# Power_supply.net
KiCad netlist of a schematic drawn in Altium Designer
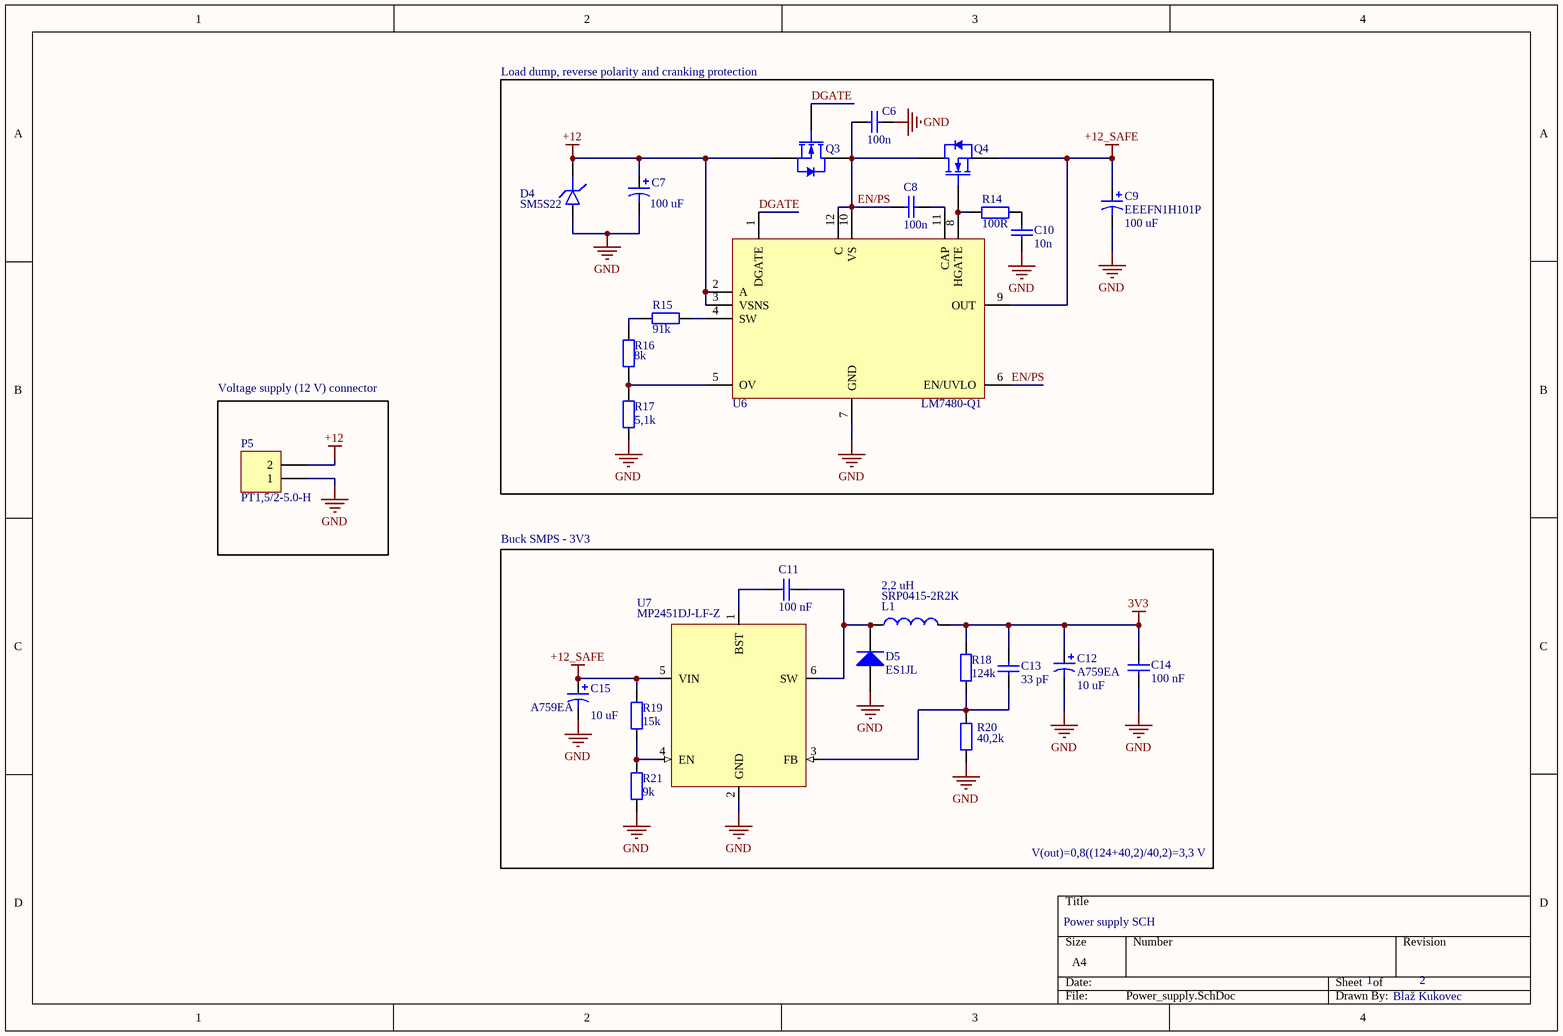
[diagram p0: Power_supply.SchDoc]

(export (version "E")
  (design (tool "Eeschema 10.0.6"))
  (components
    (comp (ref "C6")
      (value "100n")
      (footprint "C0603[1608]")
      (description "Capacitor")
      (fields (field (name "Comment") "Cap"))
      (libsource (lib "BK_Library") (part "Cap"))
    )
    (comp (ref "C7")
      (value "100 uF")
      (footprint "CAP_FN_F_PAN")
      (description "SMD Aluminium Electrolytic Capacitor, Radial Can - SMD, 100 µF, 50 V, 0.34 ohm")
      (fields (field (name "Comment") "EEEFN1H101P"))
      (libsource (lib "BK_Library") (part "EEEFN1H101P"))
    )
    (comp (ref "C8")
      (value "100n")
      (footprint "C0603[1608]")
      (description "Capacitor")
      (fields (field (name "Comment") "Cap"))
      (libsource (lib "BK_Library") (part "Cap"))
    )
    (comp (ref "C9")
      (value "EEEFN1H101P")
      (footprint "CAP_FN_F_PAN")
      (description "SMD Aluminium Electrolytic Capacitor, Radial Can - SMD, 100 µF, 50 V, 0.34 ohm")
      (fields (field (name "ALTIUM_VALUE") "100 uF"))
      (libsource (lib "") (part "EEEFN1H101P_1"))
    )
    (comp (ref "C10")
      (value "10n")
      (footprint "C0603[1608]")
      (description "Capacitor")
      (fields (field (name "Comment") "Cap"))
      (libsource (lib "BK_Library") (part "Cap"))
    )
    (comp (ref "C11")
      (value "100 nF")
      (footprint "C0603[1608]")
      (description "Capacitor")
      (fields (field (name "Comment") "Cap"))
      (libsource (lib "BK_Library") (part "Cap"))
    )
    (comp (ref "C12")
      (value "A759EA")
      (footprint "A759EA")
      (description "A759EA106M1JAAE060 - Capacitor - 10 µF - 63 V - Low ESR (60m)")
      (fields (field (name "ALTIUM_VALUE") "10 uF"))
      (libsource (lib "BK_Library") (part "A759EA106M1JAAE060"))
    )
    (comp (ref "C13")
      (value "33 pF")
      (footprint "C0603[1608]")
      (description "Capacitor")
      (fields (field (name "Comment") "Cap"))
      (libsource (lib "BK_Library") (part "Cap"))
    )
    (comp (ref "C14")
      (value "100 nF")
      (footprint "C0603[1608]")
      (description "Capacitor")
      (fields (field (name "Comment") "Cap"))
      (libsource (lib "BK_Library") (part "Cap"))
    )
    (comp (ref "C15")
      (value "A759EA")
      (footprint "A759EA")
      (description "A759EA106M1JAAE060 - Capacitor - 10 µF - 63 V - Low ESR (60m)")
      (fields (field (name "ALTIUM_VALUE") "10 uF"))
      (libsource (lib "BK_Library") (part "A759EA106M1JAAE060"))
    )
    (comp (ref "D4")
      (value "SM5S22")
      (footprint "DO-218AB_SM_VIS")
      (description "ESD Suppressors / TVS Diodes 5W,22V 5%,SMD PAR AEC-Q101 Qualified")
      (libsource (lib "BK_Library") (part "SM5S22ATHE3/I"))
    )
    (comp (ref "D5")
      (value "ES1JL")
      (footprint "Sub-SMA")
      (description "Ultrafast Diode")
      (libsource (lib "BK_Library") (part "ES1JL"))
    )
    (comp (ref "L1")
      (value "SRP0415-2R2K")
      (footprint "SRP0415")
      (description "Power Inductor (SMD), 2.2 µH, 4.2 A, Shielded, 6.5 A, SRP0415")
      (fields (field (name "ALTIUM_VALUE") "2,2 uH"))
      (libsource (lib "BK_Library") (part "SRP0415-2R2K"))
    )
    (comp (ref "P5")
      (value "PT1,5/2-5.0-H")
      (footprint "PT1,5/2-5.0-H")
      (description "Wire-To-Board Terminal Block, 5 mm, 2 Ways, 1.5 mm²")
      (libsource (lib "BK_Library") (part "PT1,5/2-5.0-H"))
    )
    (comp (ref "Q3")
      (value "BUK7Y4R8-60EX")
      (footprint "SOT669")
      (description "Power MOSFET, N Channel, 60 V, 100 A, 0.0029 ohm, LFPAK56, Surface Mount")
      (libsource (lib "BK_Library") (part "BUK7Y4R8-60EX"))
    )
    (comp (ref "Q4")
      (value "BUK7Y4R8-60EX")
      (footprint "SOT669")
      (description "Power MOSFET, N Channel, 60 V, 100 A, 0.0029 ohm, LFPAK56, Surface Mount")
      (libsource (lib "BK_Library") (part "BUK7Y4R8-60EX"))
    )
    (comp (ref "R14")
      (value "100R")
      (footprint "0603R-GENERIC")
      (description "Resistor")
      (fields (field (name "Comment") "Res"))
      (libsource (lib "") (part "Res_3"))
    )
    (comp (ref "R15")
      (value "91k")
      (footprint "R0603[1608]")
      (description "Resistor")
      (fields (field (name "Comment") "Res"))
      (libsource (lib "BK_Library") (part "Res"))
    )
    (comp (ref "R16")
      (value "8k")
      (footprint "R0603[1608]")
      (description "Resistor")
      (fields (field (name "Comment") "Res"))
      (libsource (lib "") (part "Res_2"))
    )
    (comp (ref "R17")
      (value "5,1k")
      (footprint "R0603[1608]")
      (description "Resistor")
      (fields (field (name "Comment") "Res"))
      (libsource (lib "") (part "Res_2"))
    )
    (comp (ref "R18")
      (value "124k")
      (footprint "0603R-GENERIC")
      (description "Resistor")
      (fields (field (name "Comment") "Res"))
      (libsource (lib "") (part "Res_1"))
    )
    (comp (ref "R19")
      (value "15k")
      (footprint "R0603[1608]")
      (description "Resistor")
      (fields (field (name "Comment") "Res"))
      (libsource (lib "") (part "Res_2"))
    )
    (comp (ref "R20")
      (value "40,2k")
      (footprint "0603R-GENERIC")
      (description "Resistor")
      (fields (field (name "Comment") "Res"))
      (libsource (lib "") (part "Res_2"))
    )
    (comp (ref "R21")
      (value "9k")
      (footprint "R0603[1608]")
      (description "Resistor")
      (fields (field (name "Comment") "Res"))
      (libsource (lib "") (part "Res_2"))
    )
    (comp (ref "U6")
      (value "LM7480-Q1")
      (footprint "WSON12")
      (libsource (lib "BK_Library") (part "LM7480-Q1"))
    )
    (comp (ref "U7")
      (value "MP2451DJ-LF-Z")
      (footprint "TSOT-23-6")
      (libsource (lib "BK_Library") (part "MP2451DJ-LF-Z"))
    )
  )
  (nets
    (net (code "1") (name "+12") (class "Default")
      (node (ref "C7") (pin "1") (pinfunction "1_1") (pintype "passive"))
      (node (ref "D4") (pin "K") (pinfunction "K_K") (pintype "passive"))
      (node (ref "P5") (pin "2") (pinfunction "2_2") (pintype "passive"))
      (node (ref "Q3") (pin "3") (pinfunction "S_3") (pintype "passive"))
      (node (ref "U6") (pin "2") (pinfunction "A_2") (pintype "passive"))
      (node (ref "U6") (pin "3") (pinfunction "VSNS_3") (pintype "passive"))
    )
    (net (code "2") (name "+12_SAFE") (class "Default")
      (node (ref "C15") (pin "1") (pinfunction "1_1") (pintype "passive"))
      (node (ref "C9") (pin "1") (pinfunction "1_1") (pintype "passive"))
      (node (ref "Q4") (pin "3") (pinfunction "S_3") (pintype "passive"))
      (node (ref "R19") (pin "2") (pinfunction "2_2") (pintype "passive"))
      (node (ref "U6") (pin "9") (pinfunction "OUT_9") (pintype "passive"))
      (node (ref "U7") (pin "5") (pinfunction "VIN_5") (pintype "power_in"))
    )
    (net (code "3") (name "/DGATE") (class "Default")
      (node (ref "Q3") (pin "1") (pinfunction "G_1") (pintype "passive"))
      (node (ref "U6") (pin "1") (pinfunction "_DGATE_1") (pintype "passive"))
    )
    (net (code "4") (name "/EN{slash}PS") (class "Default")
      (node (ref "C6") (pin "2") (pinfunction "2_2") (pintype "passive"))
      (node (ref "C8") (pin "1") (pinfunction "1_1") (pintype "passive"))
      (node (ref "Q3") (pin "2") (pinfunction "D_2") (pintype "passive"))
      (node (ref "Q4") (pin "2") (pinfunction "D_2") (pintype "passive"))
      (node (ref "U6") (pin "10") (pinfunction "VS_10") (pintype "passive"))
      (node (ref "U6") (pin "12") (pinfunction "C_12") (pintype "passive"))
      (node (ref "U6") (pin "6") (pinfunction "EN/UVLO_6") (pintype "passive"))
    )
    (net (code "5") (name "3V3") (class "Default")
      (node (ref "C12") (pin "1") (pinfunction "1_1") (pintype "passive"))
      (node (ref "C13") (pin "2") (pinfunction "2_2") (pintype "passive"))
      (node (ref "C14") (pin "2") (pinfunction "2_2") (pintype "passive"))
      (node (ref "L1") (pin "2") (pinfunction "2_2") (pintype "passive"))
      (node (ref "R18") (pin "1") (pinfunction "1_1") (pintype "passive"))
    )
    (net (code "6") (name "GND") (class "Default")
      (node (ref "C10") (pin "1") (pinfunction "1_1") (pintype "passive"))
      (node (ref "C12") (pin "2") (pinfunction "2_2") (pintype "passive"))
      (node (ref "C14") (pin "1") (pinfunction "1_1") (pintype "passive"))
      (node (ref "C15") (pin "2") (pinfunction "2_2") (pintype "passive"))
      (node (ref "C6") (pin "1") (pinfunction "1_1") (pintype "passive"))
      (node (ref "C7") (pin "2") (pinfunction "2_2") (pintype "passive"))
      (node (ref "C9") (pin "2") (pinfunction "2_2") (pintype "passive"))
      (node (ref "D4") (pin "A") (pinfunction "A_A") (pintype "passive"))
      (node (ref "D5") (pin "1") (pinfunction "A_1") (pintype "passive"))
      (node (ref "P5") (pin "1") (pinfunction "1_1") (pintype "passive"))
      (node (ref "R17") (pin "1") (pinfunction "1_1") (pintype "passive"))
      (node (ref "R20") (pin "1") (pinfunction "1_1") (pintype "passive"))
      (node (ref "R21") (pin "1") (pinfunction "1_1") (pintype "passive"))
      (node (ref "U6") (pin "7") (pinfunction "GND_7") (pintype "passive"))
      (node (ref "U7") (pin "2") (pinfunction "GND_2") (pintype "power_in"))
    )
    (net (code "7") (name "Net-(C10-Pad2)") (class "Default")
      (node (ref "C10") (pin "2") (pinfunction "2_2") (pintype "passive"))
      (node (ref "R14") (pin "2") (pinfunction "2_2") (pintype "passive"))
    )
    (net (code "8") (name "Net-(D5-K)") (class "Default")
      (node (ref "C11") (pin "1") (pinfunction "1_1") (pintype "passive"))
      (node (ref "D5") (pin "2") (pinfunction "K_2") (pintype "passive"))
      (node (ref "L1") (pin "1") (pinfunction "1_1") (pintype "passive"))
      (node (ref "U7") (pin "6") (pinfunction "SW_6") (pintype "power_in"))
    )
    (net (code "9") (name "Net-(Q4-G)") (class "Default")
      (node (ref "Q4") (pin "1") (pinfunction "G_1") (pintype "passive"))
      (node (ref "R14") (pin "1") (pinfunction "1_1") (pintype "passive"))
      (node (ref "U6") (pin "8") (pinfunction "HGATE_8") (pintype "passive"))
    )
    (net (code "10") (name "Net-(R15-Pad2)") (class "Default")
      (node (ref "R15") (pin "2") (pinfunction "2_2") (pintype "passive"))
      (node (ref "R16") (pin "2") (pinfunction "2_2") (pintype "passive"))
    )
    (net (code "11") (name "Net-(U6-CAP)") (class "Default")
      (node (ref "C8") (pin "2") (pinfunction "2_2") (pintype "passive"))
      (node (ref "U6") (pin "11") (pinfunction "CAP_11") (pintype "passive"))
    )
    (net (code "12") (name "Net-(U6-OV)") (class "Default")
      (node (ref "R16") (pin "1") (pinfunction "1_1") (pintype "passive"))
      (node (ref "R17") (pin "2") (pinfunction "2_2") (pintype "passive"))
      (node (ref "U6") (pin "5") (pinfunction "OV_5") (pintype "passive"))
    )
    (net (code "13") (name "Net-(U6-SW)") (class "Default")
      (node (ref "R15") (pin "1") (pinfunction "1_1") (pintype "passive"))
      (node (ref "U6") (pin "4") (pinfunction "SW_4") (pintype "passive"))
    )
    (net (code "14") (name "Net-(U7-BST)") (class "Default")
      (node (ref "C11") (pin "2") (pinfunction "2_2") (pintype "passive"))
      (node (ref "U7") (pin "1") (pinfunction "BST_1") (pintype "power_in"))
    )
    (net (code "15") (name "Net-(U7-EN)") (class "Default")
      (node (ref "R19") (pin "1") (pinfunction "1_1") (pintype "passive"))
      (node (ref "R21") (pin "2") (pinfunction "2_2") (pintype "passive"))
      (node (ref "U7") (pin "4") (pinfunction "EN_4") (pintype "input"))
    )
    (net (code "16") (name "Net-(U7-FB)") (class "Default")
      (node (ref "C13") (pin "1") (pinfunction "1_1") (pintype "passive"))
      (node (ref "R18") (pin "2") (pinfunction "2_2") (pintype "passive"))
      (node (ref "R20") (pin "2") (pinfunction "2_2") (pintype "passive"))
      (node (ref "U7") (pin "3") (pinfunction "FB_3") (pintype "input"))
    )
  )
)
